# k26_baseboard_power_supply.net
KiCad netlist of a schematic drawn in Altium Designer
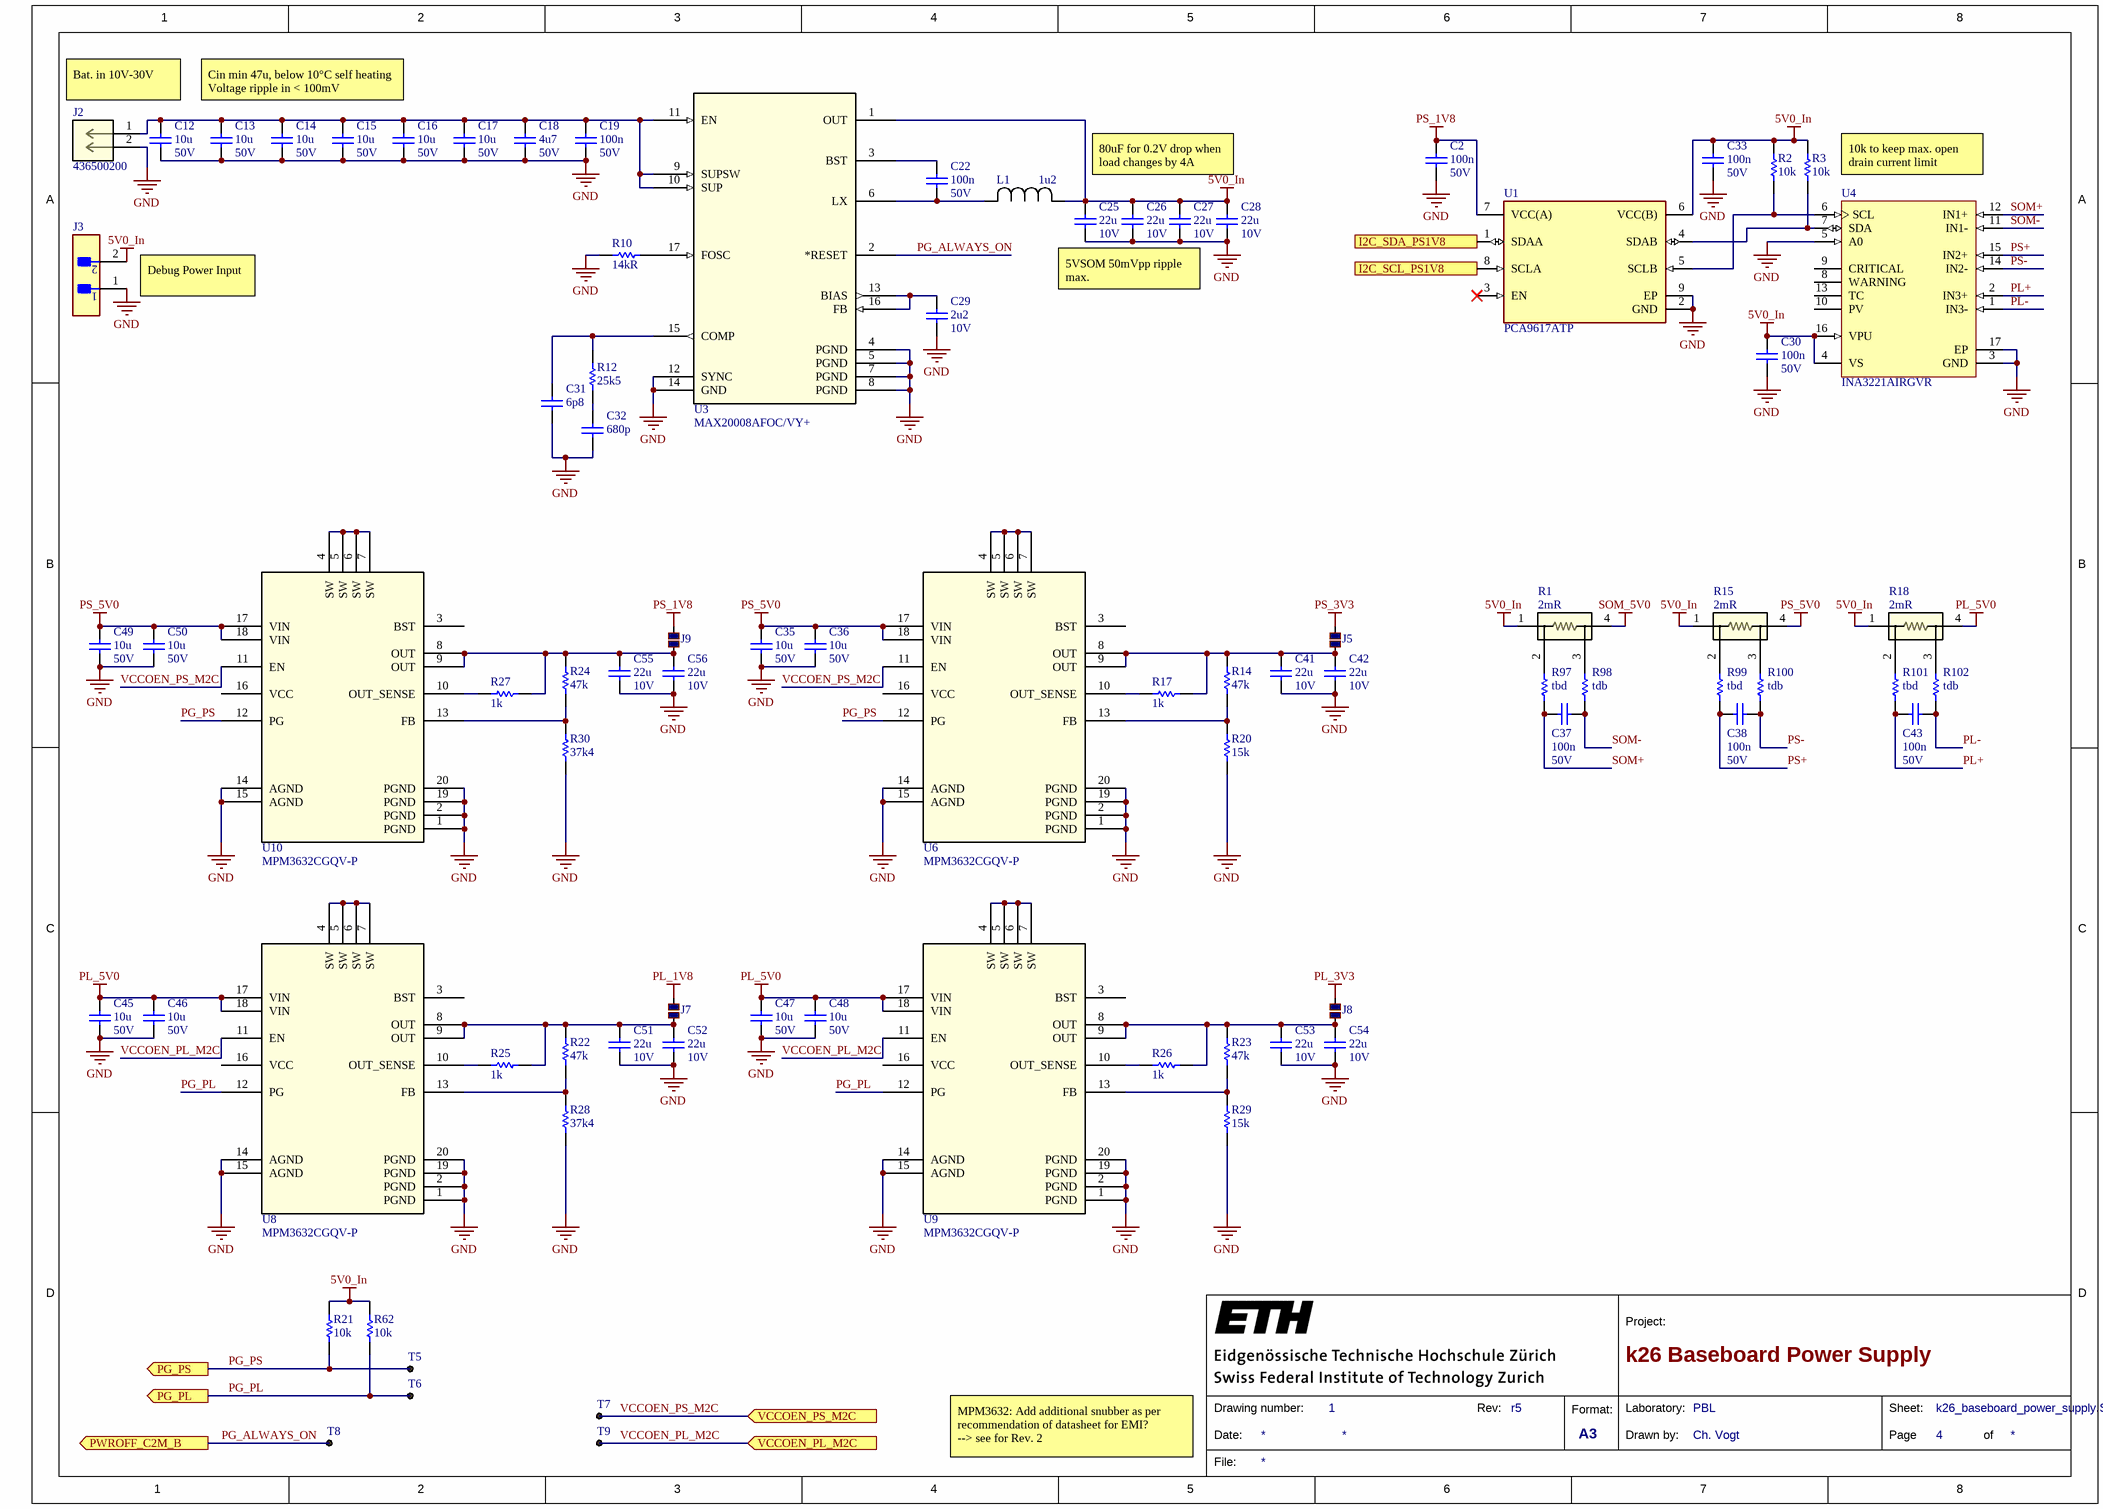
[diagram p0: k26_baseboard_power_supply.SchDoc]

(export (version "E")
  (design (tool "Eeschema 10.0.6"))
  (components
    (comp (ref "C2")
      (value "100n")
      (footprint "k26_FPGA_drone_baseboard:CAPC0402")
      (fields
        (field (name "MANUFACTURER") "Yageo")
        (field (name "MANUFACTURER PART NUMBER") "CC0402KRX5R9BB104")
        (field (name "RATED DC VOLTAGE (URDC)") "50V")
      )
      (libsource (lib "k26_FPGA_drone_baseboard") (part "cap0402"))
    )
    (comp (ref "C12")
      (value "10u")
      (footprint "k26_FPGA_drone_baseboard:CAPC1206")
      (fields
        (field (name "MANUFACTURER") "Murata")
        (field (name "MANUFACTURER PART NUMBER") "GRM31CR61H106KA12L")
        (field (name "RATED DC VOLTAGE (URDC)") "50V")
      )
      (libsource (lib "k26_FPGA_drone_baseboard") (part "cap1206"))
    )
    (comp (ref "C13")
      (value "10u")
      (footprint "k26_FPGA_drone_baseboard:CAPC1206")
      (fields
        (field (name "MANUFACTURER") "Murata")
        (field (name "MANUFACTURER PART NUMBER") "GRM31CR61H106KA12L")
        (field (name "RATED DC VOLTAGE (URDC)") "50V")
      )
      (libsource (lib "k26_FPGA_drone_baseboard") (part "cap1206"))
    )
    (comp (ref "C14")
      (value "10u")
      (footprint "k26_FPGA_drone_baseboard:CAPC1206")
      (fields
        (field (name "MANUFACTURER") "Murata")
        (field (name "MANUFACTURER PART NUMBER") "GRM31CR61H106KA12L")
        (field (name "RATED DC VOLTAGE (URDC)") "50V")
      )
      (libsource (lib "k26_FPGA_drone_baseboard") (part "cap1206"))
    )
    (comp (ref "C15")
      (value "10u")
      (footprint "k26_FPGA_drone_baseboard:CAPC1206")
      (fields
        (field (name "MANUFACTURER") "Murata")
        (field (name "MANUFACTURER PART NUMBER") "GRM31CR61H106KA12L")
        (field (name "RATED DC VOLTAGE (URDC)") "50V")
      )
      (libsource (lib "k26_FPGA_drone_baseboard") (part "cap1206"))
    )
    (comp (ref "C16")
      (value "10u")
      (footprint "k26_FPGA_drone_baseboard:CAPC1206")
      (fields
        (field (name "MANUFACTURER") "Murata")
        (field (name "MANUFACTURER PART NUMBER") "GRM31CR61H106KA12L")
        (field (name "RATED DC VOLTAGE (URDC)") "50V")
      )
      (libsource (lib "k26_FPGA_drone_baseboard") (part "cap1206"))
    )
    (comp (ref "C17")
      (value "10u")
      (footprint "k26_FPGA_drone_baseboard:CAPC1206")
      (fields
        (field (name "MANUFACTURER") "Murata")
        (field (name "MANUFACTURER PART NUMBER") "GRM31CR61H106KA12L")
        (field (name "RATED DC VOLTAGE (URDC)") "50V")
      )
      (libsource (lib "k26_FPGA_drone_baseboard") (part "cap1206"))
    )
    (comp (ref "C18")
      (value "4u7")
      (footprint "k26_FPGA_drone_baseboard:CAPC1206")
      (fields
        (field (name "MANUFACTURER") "Murata")
        (field (name "MANUFACTURER PART NUMBER") "GRM31CR71H475KA12L")
        (field (name "RATED DC VOLTAGE (URDC)") "50V")
      )
      (libsource (lib "k26_FPGA_drone_baseboard") (part "cap1206"))
    )
    (comp (ref "C19")
      (value "100n")
      (footprint "k26_FPGA_drone_baseboard:CAPC0402")
      (fields
        (field (name "MANUFACTURER") "Yageo")
        (field (name "MANUFACTURER PART NUMBER") "CC0402KRX5R9BB104")
        (field (name "RATED DC VOLTAGE (URDC)") "50V")
      )
      (libsource (lib "k26_FPGA_drone_baseboard") (part "cap0402"))
    )
    (comp (ref "C22")
      (value "100n")
      (footprint "k26_FPGA_drone_baseboard:CAPC0402")
      (fields
        (field (name "MANUFACTURER") "Yageo")
        (field (name "MANUFACTURER PART NUMBER") "CC0402KRX5R9BB104")
        (field (name "RATED DC VOLTAGE (URDC)") "50V")
      )
      (libsource (lib "k26_FPGA_drone_baseboard") (part "cap0402"))
    )
    (comp (ref "C25")
      (value "22u")
      (footprint "k26_FPGA_drone_baseboard:CAPC1206")
      (fields
        (field (name "MANUFACTURER") "Kyocera AVX")
        (field (name "MANUFACTURER PART NUMBER") "1206ZC226KAT2A")
        (field (name "RATED DC VOLTAGE (URDC)") "10V")
      )
      (libsource (lib "k26_FPGA_drone_baseboard") (part "cap1206"))
    )
    (comp (ref "C26")
      (value "22u")
      (footprint "k26_FPGA_drone_baseboard:CAPC1206")
      (fields
        (field (name "MANUFACTURER") "Kyocera AVX")
        (field (name "MANUFACTURER PART NUMBER") "1206ZC226KAT2A")
        (field (name "RATED DC VOLTAGE (URDC)") "10V")
      )
      (libsource (lib "k26_FPGA_drone_baseboard") (part "cap1206"))
    )
    (comp (ref "C27")
      (value "22u")
      (footprint "k26_FPGA_drone_baseboard:CAPC1206")
      (fields
        (field (name "MANUFACTURER") "Kyocera AVX")
        (field (name "MANUFACTURER PART NUMBER") "1206ZC226KAT2A")
        (field (name "RATED DC VOLTAGE (URDC)") "10V")
      )
      (libsource (lib "k26_FPGA_drone_baseboard") (part "cap1206"))
    )
    (comp (ref "C28")
      (value "22u")
      (footprint "k26_FPGA_drone_baseboard:CAPC1206")
      (fields
        (field (name "MANUFACTURER") "Kyocera AVX")
        (field (name "MANUFACTURER PART NUMBER") "1206ZC226KAT2A")
        (field (name "RATED DC VOLTAGE (URDC)") "10V")
      )
      (libsource (lib "k26_FPGA_drone_baseboard") (part "cap1206"))
    )
    (comp (ref "C29")
      (value "2u2")
      (footprint "k26_FPGA_drone_baseboard:CAPC0402")
      (fields
        (field (name "MANUFACTURER") "TDK")
        (field (name "MANUFACTURER PART NUMBER") "C1005X7S1A225K050BC")
        (field (name "RATED DC VOLTAGE (URDC)") "10V")
      )
      (libsource (lib "k26_FPGA_drone_baseboard") (part "cap0402"))
    )
    (comp (ref "C30")
      (value "100n")
      (footprint "k26_FPGA_drone_baseboard:CAPC0402")
      (fields
        (field (name "MANUFACTURER") "Yageo")
        (field (name "MANUFACTURER PART NUMBER") "CC0402KRX5R9BB104")
        (field (name "RATED DC VOLTAGE (URDC)") "50V")
      )
      (libsource (lib "k26_FPGA_drone_baseboard") (part "cap0402"))
    )
    (comp (ref "C31")
      (value "6p8")
      (footprint "k26_FPGA_drone_baseboard:CAPC0402")
      (fields
        (field (name "MANUFACTURER") "Kyocera AVX")
        (field (name "MANUFACTURER PART NUMBER") "04025A6R8CAT2A")
      )
      (libsource (lib "k26_FPGA_drone_baseboard") (part "cap0402"))
    )
    (comp (ref "C32")
      (value "680p")
      (footprint "k26_FPGA_drone_baseboard:CAPC0402")
      (fields
        (field (name "MANUFACTURER") "Kyocera AVX")
        (field (name "MANUFACTURER PART NUMBER") "04025C681KAT2A")
      )
      (libsource (lib "k26_FPGA_drone_baseboard") (part "cap0402"))
    )
    (comp (ref "C33")
      (value "100n")
      (footprint "k26_FPGA_drone_baseboard:CAPC0402")
      (fields
        (field (name "MANUFACTURER") "Yageo")
        (field (name "MANUFACTURER PART NUMBER") "CC0402KRX5R9BB104")
        (field (name "RATED DC VOLTAGE (URDC)") "50V")
      )
      (libsource (lib "k26_FPGA_drone_baseboard") (part "cap0402"))
    )
    (comp (ref "C35")
      (value "10u")
      (footprint "k26_FPGA_drone_baseboard:CAPC1206")
      (fields
        (field (name "MANUFACTURER") "Murata")
        (field (name "MANUFACTURER PART NUMBER") "GRM31CR61H106KA12L")
        (field (name "RATED DC VOLTAGE (URDC)") "50V")
      )
      (libsource (lib "k26_FPGA_drone_baseboard") (part "cap1206"))
    )
    (comp (ref "C36")
      (value "10u")
      (footprint "k26_FPGA_drone_baseboard:CAPC1206")
      (fields
        (field (name "MANUFACTURER") "Murata")
        (field (name "MANUFACTURER PART NUMBER") "GRM31CR61H106KA12L")
        (field (name "RATED DC VOLTAGE (URDC)") "50V")
      )
      (libsource (lib "k26_FPGA_drone_baseboard") (part "cap1206"))
    )
    (comp (ref "C37")
      (value "100n")
      (footprint "k26_FPGA_drone_baseboard:CAPC0402")
      (fields
        (field (name "MANUFACTURER") "Yageo")
        (field (name "MANUFACTURER PART NUMBER") "CC0402KRX5R9BB104")
        (field (name "RATED DC VOLTAGE (URDC)") "50V")
      )
      (libsource (lib "k26_FPGA_drone_baseboard") (part "cap0402"))
    )
    (comp (ref "C38")
      (value "100n")
      (footprint "k26_FPGA_drone_baseboard:CAPC0402")
      (fields
        (field (name "MANUFACTURER") "Yageo")
        (field (name "MANUFACTURER PART NUMBER") "CC0402KRX5R9BB104")
        (field (name "RATED DC VOLTAGE (URDC)") "50V")
      )
      (libsource (lib "k26_FPGA_drone_baseboard") (part "cap0402"))
    )
    (comp (ref "C41")
      (value "22u")
      (footprint "k26_FPGA_drone_baseboard:CAPC1206")
      (fields
        (field (name "MANUFACTURER") "Kyocera AVX")
        (field (name "MANUFACTURER PART NUMBER") "1206ZC226KAT2A")
        (field (name "RATED DC VOLTAGE (URDC)") "10V")
      )
      (libsource (lib "k26_FPGA_drone_baseboard") (part "cap1206"))
    )
    (comp (ref "C42")
      (value "22u")
      (footprint "k26_FPGA_drone_baseboard:CAPC1206")
      (fields
        (field (name "MANUFACTURER") "Kyocera AVX")
        (field (name "MANUFACTURER PART NUMBER") "1206ZC226KAT2A")
        (field (name "RATED DC VOLTAGE (URDC)") "10V")
      )
      (libsource (lib "k26_FPGA_drone_baseboard") (part "cap1206"))
    )
    (comp (ref "C43")
      (value "100n")
      (footprint "k26_FPGA_drone_baseboard:CAPC0402")
      (fields
        (field (name "MANUFACTURER") "Yageo")
        (field (name "MANUFACTURER PART NUMBER") "CC0402KRX5R9BB104")
        (field (name "RATED DC VOLTAGE (URDC)") "50V")
      )
      (libsource (lib "k26_FPGA_drone_baseboard") (part "cap0402"))
    )
    (comp (ref "C45")
      (value "10u")
      (footprint "k26_FPGA_drone_baseboard:CAPC1206")
      (fields
        (field (name "MANUFACTURER") "Murata")
        (field (name "MANUFACTURER PART NUMBER") "GRM31CR61H106KA12L")
        (field (name "RATED DC VOLTAGE (URDC)") "50V")
      )
      (libsource (lib "k26_FPGA_drone_baseboard") (part "cap1206"))
    )
    (comp (ref "C46")
      (value "10u")
      (footprint "k26_FPGA_drone_baseboard:CAPC1206")
      (fields
        (field (name "MANUFACTURER") "Murata")
        (field (name "MANUFACTURER PART NUMBER") "GRM31CR61H106KA12L")
        (field (name "RATED DC VOLTAGE (URDC)") "50V")
      )
      (libsource (lib "k26_FPGA_drone_baseboard") (part "cap1206"))
    )
    (comp (ref "C47")
      (value "10u")
      (footprint "k26_FPGA_drone_baseboard:CAPC1206")
      (fields
        (field (name "MANUFACTURER") "Murata")
        (field (name "MANUFACTURER PART NUMBER") "GRM31CR61H106KA12L")
        (field (name "RATED DC VOLTAGE (URDC)") "50V")
      )
      (libsource (lib "k26_FPGA_drone_baseboard") (part "cap1206"))
    )
    (comp (ref "C48")
      (value "10u")
      (footprint "k26_FPGA_drone_baseboard:CAPC1206")
      (fields
        (field (name "MANUFACTURER") "Murata")
        (field (name "MANUFACTURER PART NUMBER") "GRM31CR61H106KA12L")
        (field (name "RATED DC VOLTAGE (URDC)") "50V")
      )
      (libsource (lib "k26_FPGA_drone_baseboard") (part "cap1206"))
    )
    (comp (ref "C49")
      (value "10u")
      (footprint "k26_FPGA_drone_baseboard:CAPC1206")
      (fields
        (field (name "MANUFACTURER") "Murata")
        (field (name "MANUFACTURER PART NUMBER") "GRM31CR61H106KA12L")
        (field (name "RATED DC VOLTAGE (URDC)") "50V")
      )
      (libsource (lib "k26_FPGA_drone_baseboard") (part "cap1206"))
    )
    (comp (ref "C50")
      (value "10u")
      (footprint "k26_FPGA_drone_baseboard:CAPC1206")
      (fields
        (field (name "MANUFACTURER") "Murata")
        (field (name "MANUFACTURER PART NUMBER") "GRM31CR61H106KA12L")
        (field (name "RATED DC VOLTAGE (URDC)") "50V")
      )
      (libsource (lib "k26_FPGA_drone_baseboard") (part "cap1206"))
    )
    (comp (ref "C51")
      (value "22u")
      (footprint "k26_FPGA_drone_baseboard:CAPC1206")
      (fields
        (field (name "MANUFACTURER") "Kyocera AVX")
        (field (name "MANUFACTURER PART NUMBER") "1206ZC226KAT2A")
        (field (name "RATED DC VOLTAGE (URDC)") "10V")
      )
      (libsource (lib "k26_FPGA_drone_baseboard") (part "cap1206"))
    )
    (comp (ref "C52")
      (value "22u")
      (footprint "k26_FPGA_drone_baseboard:CAPC1206")
      (fields
        (field (name "MANUFACTURER") "Kyocera AVX")
        (field (name "MANUFACTURER PART NUMBER") "1206ZC226KAT2A")
        (field (name "RATED DC VOLTAGE (URDC)") "10V")
      )
      (libsource (lib "k26_FPGA_drone_baseboard") (part "cap1206"))
    )
    (comp (ref "C53")
      (value "22u")
      (footprint "k26_FPGA_drone_baseboard:CAPC1206")
      (fields
        (field (name "MANUFACTURER") "Kyocera AVX")
        (field (name "MANUFACTURER PART NUMBER") "1206ZC226KAT2A")
        (field (name "RATED DC VOLTAGE (URDC)") "10V")
      )
      (libsource (lib "k26_FPGA_drone_baseboard") (part "cap1206"))
    )
    (comp (ref "C54")
      (value "22u")
      (footprint "k26_FPGA_drone_baseboard:CAPC1206")
      (fields
        (field (name "MANUFACTURER") "Kyocera AVX")
        (field (name "MANUFACTURER PART NUMBER") "1206ZC226KAT2A")
        (field (name "RATED DC VOLTAGE (URDC)") "10V")
      )
      (libsource (lib "k26_FPGA_drone_baseboard") (part "cap1206"))
    )
    (comp (ref "C55")
      (value "22u")
      (footprint "k26_FPGA_drone_baseboard:CAPC1206")
      (fields
        (field (name "MANUFACTURER") "Kyocera AVX")
        (field (name "MANUFACTURER PART NUMBER") "1206ZC226KAT2A")
        (field (name "RATED DC VOLTAGE (URDC)") "10V")
      )
      (libsource (lib "k26_FPGA_drone_baseboard") (part "cap1206"))
    )
    (comp (ref "C56")
      (value "22u")
      (footprint "k26_FPGA_drone_baseboard:CAPC1206")
      (fields
        (field (name "MANUFACTURER") "Kyocera AVX")
        (field (name "MANUFACTURER PART NUMBER") "1206ZC226KAT2A")
        (field (name "RATED DC VOLTAGE (URDC)") "10V")
      )
      (libsource (lib "k26_FPGA_drone_baseboard") (part "cap1206"))
    )
    (comp (ref "J2")
      (value "436500200")
      (footprint "CON_436500200_MOL")
      (description "Board Connector, 2 Contact(s), 1 Row(s), Male, Right Angle, Solder Terminal")
      (fields
        (field (name "MANUFACTURER") "Molex")
        (field (name "MANUFACTURER PART NUMBER") "0436500200")
        (field (name "COPYRIGHT") "Copyright (C) 2024 Ultra Librarian. All rights reserved.")
      )
      (libsource (lib "k26_FPGA_drone_baseboard") (part "436500200"))
    )
    (comp (ref "J3")
      (value "~")
      (footprint "FP-TSW-102-07-S-S-MFG")
      (description "CONN HEADER VERT 2POS 2.54MM")
      (libsource (lib "k26_FPGA_drone_baseboard") (part "3bc925449376181038e59eaffc5286c"))
    )
    (comp (ref "J5")
      (value "CMP-00005-5")
      (footprint "Big Solder Jumper")
      (libsource (lib "k26_FPGA_drone_baseboard") (part "CMP-00005-5"))
    )
    (comp (ref "J7")
      (value "CMP-00005-5")
      (footprint "Big Solder Jumper")
      (libsource (lib "k26_FPGA_drone_baseboard") (part "CMP-00005-5"))
    )
    (comp (ref "J8")
      (value "CMP-00005-5")
      (footprint "Big Solder Jumper")
      (libsource (lib "k26_FPGA_drone_baseboard") (part "CMP-00005-5"))
    )
    (comp (ref "J9")
      (value "CMP-00005-5")
      (footprint "Big Solder Jumper")
      (libsource (lib "k26_FPGA_drone_baseboard") (part "CMP-00005-5"))
    )
    (comp (ref "L1")
      (value "XGL5050-122MEC")
      (footprint "IND_XGL5050_COC")
      (description "General Purpose Inductor, 1.2uH, 20%, 1 Element, Composite-Core, SMD, 2221")
      (fields
        (field (name "MANUFACTURER") "Coilcraft")
        (field (name "PARAMETER 1") "1u2")
        (field (name "COPYRIGHT") "Copyright (C) 2023 Ultra Librarian. All rights reserved.")
      )
      (libsource (lib "k26_FPGA_drone_baseboard") (part "XGL5050-122MEC"))
    )
    (comp (ref "R1")
      (value "CST0612-FC-R002E")
      (footprint "CST0612-FC-R002E_BRN")
      (description "No Description Available")
      (fields
        (field (name "RES") "2mR")
        (field (name "COPYRIGHT") "Copyright (C) 2023 Ultra Librarian. All rights reserved.")
      )
      (libsource (lib "k26_FPGA_drone_baseboard") (part "CST0612-FC-R002E"))
    )
    (comp (ref "R2")
      (value "10k")
      (footprint "k26_FPGA_drone_baseboard:RES0402")
      (fields
        (field (name "MANUFACTURER") "Panasonic")
        (field (name "MANUFACTURER PART NUMBER") "ERJ-2RKF1002X")
        (field (name "TOLERANCE") "1%")
      )
      (libsource (lib "k26_FPGA_drone_baseboard") (part "res0402"))
    )
    (comp (ref "R3")
      (value "10k")
      (footprint "k26_FPGA_drone_baseboard:RES0402")
      (fields
        (field (name "MANUFACTURER") "Panasonic")
        (field (name "MANUFACTURER PART NUMBER") "ERJ-2RKF1002X")
        (field (name "TOLERANCE") "1%")
      )
      (libsource (lib "k26_FPGA_drone_baseboard") (part "res0402"))
    )
    (comp (ref "R10")
      (value "14kR")
      (footprint "k26_FPGA_drone_baseboard:RES0402")
      (fields
        (field (name "MANUFACTURER") "Vishay")
        (field (name "MANUFACTURER PART NUMBER") "CRCW040214K0FKED")
        (field (name "TOLERANCE") "1%")
      )
      (libsource (lib "k26_FPGA_drone_baseboard") (part "res0402"))
    )
    (comp (ref "R12")
      (value "25k5")
      (footprint "k26_FPGA_drone_baseboard:RES0402")
      (fields
        (field (name "MANUFACTURER") "Vishay")
        (field (name "MANUFACTURER PART NUMBER") "CRCW040225K5FKED")
        (field (name "TOLERANCE") "1%")
      )
      (libsource (lib "k26_FPGA_drone_baseboard") (part "res0402"))
    )
    (comp (ref "R14")
      (value "47k")
      (footprint "k26_FPGA_drone_baseboard:RES0402")
      (fields
        (field (name "MANUFACTURER") "Vishay")
        (field (name "MANUFACTURER PART NUMBER") "CRCW040247K0FKED")
        (field (name "TOLERANCE") "1%")
      )
      (libsource (lib "k26_FPGA_drone_baseboard") (part "res0402"))
    )
    (comp (ref "R15")
      (value "CST0612-FC-R002E")
      (footprint "CST0612-FC-R002E_BRN")
      (description "No Description Available")
      (fields
        (field (name "RES") "2mR")
        (field (name "COPYRIGHT") "Copyright (C) 2023 Ultra Librarian. All rights reserved.")
      )
      (libsource (lib "k26_FPGA_drone_baseboard") (part "CST0612-FC-R002E"))
    )
    (comp (ref "R17")
      (value "1k")
      (footprint "k26_FPGA_drone_baseboard:RES0402")
      (fields
        (field (name "MANUFACTURER") "Yageo")
        (field (name "MANUFACTURER PART NUMBER") "RC0402FR-071KL")
        (field (name "TOLERANCE") "1%")
      )
      (libsource (lib "k26_FPGA_drone_baseboard") (part "res0402"))
    )
    (comp (ref "R18")
      (value "CST0612-FC-R002E")
      (footprint "CST0612-FC-R002E_BRN")
      (description "No Description Available")
      (fields
        (field (name "RES") "2mR")
        (field (name "COPYRIGHT") "Copyright (C) 2023 Ultra Librarian. All rights reserved.")
      )
      (libsource (lib "k26_FPGA_drone_baseboard") (part "CST0612-FC-R002E"))
    )
    (comp (ref "R20")
      (value "15k")
      (footprint "k26_FPGA_drone_baseboard:RES0402")
      (fields
        (field (name "MANUFACTURER") "Panasonic")
        (field (name "MANUFACTURER PART NUMBER") "ERJ-2RKF1502X")
        (field (name "TOLERANCE") "1%")
      )
      (libsource (lib "k26_FPGA_drone_baseboard") (part "res0402"))
    )
    (comp (ref "R21")
      (value "10k")
      (footprint "k26_FPGA_drone_baseboard:RES0402")
      (fields
        (field (name "MANUFACTURER") "Panasonic")
        (field (name "MANUFACTURER PART NUMBER") "ERJ-2RKF1002X")
        (field (name "TOLERANCE") "1%")
      )
      (libsource (lib "k26_FPGA_drone_baseboard") (part "res0402"))
    )
    (comp (ref "R22")
      (value "47k")
      (footprint "k26_FPGA_drone_baseboard:RES0402")
      (fields
        (field (name "MANUFACTURER") "Vishay")
        (field (name "MANUFACTURER PART NUMBER") "CRCW040247K0FKED")
        (field (name "TOLERANCE") "1%")
      )
      (libsource (lib "k26_FPGA_drone_baseboard") (part "res0402"))
    )
    (comp (ref "R23")
      (value "47k")
      (footprint "k26_FPGA_drone_baseboard:RES0402")
      (fields
        (field (name "MANUFACTURER") "Vishay")
        (field (name "MANUFACTURER PART NUMBER") "CRCW040247K0FKED")
        (field (name "TOLERANCE") "1%")
      )
      (libsource (lib "k26_FPGA_drone_baseboard") (part "res0402"))
    )
    (comp (ref "R24")
      (value "47k")
      (footprint "k26_FPGA_drone_baseboard:RES0402")
      (fields
        (field (name "MANUFACTURER") "Vishay")
        (field (name "MANUFACTURER PART NUMBER") "CRCW040247K0FKED")
        (field (name "TOLERANCE") "1%")
      )
      (libsource (lib "k26_FPGA_drone_baseboard") (part "res0402"))
    )
    (comp (ref "R25")
      (value "1k")
      (footprint "k26_FPGA_drone_baseboard:RES0402")
      (fields
        (field (name "MANUFACTURER") "Yageo")
        (field (name "MANUFACTURER PART NUMBER") "RC0402FR-071KL")
        (field (name "TOLERANCE") "1%")
      )
      (libsource (lib "k26_FPGA_drone_baseboard") (part "res0402"))
    )
    (comp (ref "R26")
      (value "1k")
      (footprint "k26_FPGA_drone_baseboard:RES0402")
      (fields
        (field (name "MANUFACTURER") "Yageo")
        (field (name "MANUFACTURER PART NUMBER") "RC0402FR-071KL")
        (field (name "TOLERANCE") "1%")
      )
      (libsource (lib "k26_FPGA_drone_baseboard") (part "res0402"))
    )
    (comp (ref "R27")
      (value "1k")
      (footprint "k26_FPGA_drone_baseboard:RES0402")
      (fields
        (field (name "MANUFACTURER") "Yageo")
        (field (name "MANUFACTURER PART NUMBER") "RC0402FR-071KL")
        (field (name "TOLERANCE") "1%")
      )
      (libsource (lib "k26_FPGA_drone_baseboard") (part "res0402"))
    )
    (comp (ref "R28")
      (value "37k4")
      (footprint "k26_FPGA_drone_baseboard:RES0402")
      (fields
        (field (name "MANUFACTURER") "Panasonic")
        (field (name "MANUFACTURER PART NUMBER") "ERJ-2RKF3742X")
        (field (name "TOLERANCE") "1%")
      )
      (libsource (lib "k26_FPGA_drone_baseboard") (part "res0402"))
    )
    (comp (ref "R29")
      (value "15k")
      (footprint "k26_FPGA_drone_baseboard:RES0402")
      (fields
        (field (name "MANUFACTURER") "Panasonic")
        (field (name "MANUFACTURER PART NUMBER") "ERJ-2RKF1502X")
        (field (name "TOLERANCE") "1%")
      )
      (libsource (lib "k26_FPGA_drone_baseboard") (part "res0402"))
    )
    (comp (ref "R30")
      (value "37k4")
      (footprint "k26_FPGA_drone_baseboard:RES0402")
      (fields
        (field (name "MANUFACTURER") "Panasonic")
        (field (name "MANUFACTURER PART NUMBER") "ERJ-2RKF3742X")
        (field (name "TOLERANCE") "1%")
      )
      (libsource (lib "k26_FPGA_drone_baseboard") (part "res0402"))
    )
    (comp (ref "R62")
      (value "10k")
      (footprint "k26_FPGA_drone_baseboard:RES0402")
      (fields
        (field (name "MANUFACTURER") "Panasonic")
        (field (name "MANUFACTURER PART NUMBER") "ERJ-2RKF1002X")
        (field (name "TOLERANCE") "1%")
      )
      (libsource (lib "k26_FPGA_drone_baseboard") (part "res0402"))
    )
    (comp (ref "R97")
      (value "tbd")
      (footprint "k26_FPGA_drone_baseboard:RES0402")
      (fields
        (field (name "MANUFACTURER") "Yageo")
        (field (name "MANUFACTURER PART NUMBER") "RC0402FR-071KL")
        (field (name "TOLERANCE") "1%")
      )
      (libsource (lib "k26_FPGA_drone_baseboard") (part "res0402"))
    )
    (comp (ref "R98")
      (value "tdb")
      (footprint "k26_FPGA_drone_baseboard:RES0402")
      (fields
        (field (name "MANUFACTURER") "Yageo")
        (field (name "MANUFACTURER PART NUMBER") "RC0402FR-071KL")
        (field (name "TOLERANCE") "1%")
      )
      (libsource (lib "k26_FPGA_drone_baseboard") (part "res0402"))
    )
    (comp (ref "R99")
      (value "tbd")
      (footprint "k26_FPGA_drone_baseboard:RES0402")
      (fields
        (field (name "MANUFACTURER") "Yageo")
        (field (name "MANUFACTURER PART NUMBER") "RC0402FR-071KL")
        (field (name "TOLERANCE") "1%")
      )
      (libsource (lib "k26_FPGA_drone_baseboard") (part "res0402"))
    )
    (comp (ref "R100")
      (value "tdb")
      (footprint "k26_FPGA_drone_baseboard:RES0402")
      (fields
        (field (name "MANUFACTURER") "Yageo")
        (field (name "MANUFACTURER PART NUMBER") "RC0402FR-071KL")
        (field (name "TOLERANCE") "1%")
      )
      (libsource (lib "k26_FPGA_drone_baseboard") (part "res0402"))
    )
    (comp (ref "R101")
      (value "tbd")
      (footprint "k26_FPGA_drone_baseboard:RES0402")
      (fields
        (field (name "MANUFACTURER") "Yageo")
        (field (name "MANUFACTURER PART NUMBER") "RC0402FR-071KL")
        (field (name "TOLERANCE") "1%")
      )
      (libsource (lib "k26_FPGA_drone_baseboard") (part "res0402"))
    )
    (comp (ref "R102")
      (value "tdb")
      (footprint "k26_FPGA_drone_baseboard:RES0402")
      (fields
        (field (name "MANUFACTURER") "Yageo")
        (field (name "MANUFACTURER PART NUMBER") "RC0402FR-071KL")
        (field (name "TOLERANCE") "1%")
      )
      (libsource (lib "k26_FPGA_drone_baseboard") (part "res0402"))
    )
    (comp (ref "T5")
      (value "~")
      (footprint "Pad-1mm")
      (description "1mm SMT Test Pad")
      (libsource (lib "k26_FPGA_drone_baseboard") (part "Test Pad"))
    )
    (comp (ref "T6")
      (value "~")
      (footprint "Pad-1mm")
      (description "1mm SMT Test Pad")
      (libsource (lib "k26_FPGA_drone_baseboard") (part "Test Pad"))
    )
    (comp (ref "T7")
      (value "~")
      (footprint "Pad-1mm")
      (description "1mm SMT Test Pad")
      (libsource (lib "k26_FPGA_drone_baseboard") (part "Test Pad"))
    )
    (comp (ref "T8")
      (value "~")
      (footprint "Pad-1mm")
      (description "1mm SMT Test Pad")
      (libsource (lib "k26_FPGA_drone_baseboard") (part "Test Pad"))
    )
    (comp (ref "T9")
      (value "~")
      (footprint "Pad-1mm")
      (description "1mm SMT Test Pad")
      (libsource (lib "k26_FPGA_drone_baseboard") (part "Test Pad"))
    )
    (comp (ref "U1")
      (value "PCA9617ATP")
      (footprint "FP-SOT1069-2-MFG")
      (description "IC REDRIVER I2C 1CH 1MHZ 8HWSON")
      (libsource (lib "k26_FPGA_drone_baseboard") (part "91d4d44e6b01ffaf70a860af717f933"))
    )
    (comp (ref "U3")
      (value "MAX20008AFOC/VY+")
      (footprint "21-100155B_F173A3FY+1_MXM")
      (description "No Description Available")
      (fields (field (name "COPYRIGHT") "Copyright (C) 2022 Ultra Librarian. All rights reserved."))
      (libsource (lib "k26_FPGA_drone_baseboard") (part "MAX20008AFOC/VY+"))
    )
    (comp (ref "U4")
      (value "INA3221AIRGVR")
      (footprint "RGV0016A_V")
      (fields (field (name "MANUFACTURER") "Texas Instruments"))
      (libsource (lib "k26_FPGA_drone_baseboard") (part "TI-INA3221-RGV-16"))
    )
    (comp (ref "U6")
      (value "MPM3632CGQV-P")
      (footprint "k26_FPGA_drone_baseboard:QFN3p0x5p0x1p6_MPM3632C_MNP")
      (description "No Description Available")
      (fields (field (name "COPYRIGHT") "Copyright (C) 2022 Ultra Librarian. All rights reserved."))
      (libsource (lib "k26_FPGA_drone_baseboard") (part "MPM3632CGQV-P"))
    )
    (comp (ref "U8")
      (value "MPM3632CGQV-P")
      (footprint "k26_FPGA_drone_baseboard:QFN3p0x5p0x1p6_MPM3632C_MNP")
      (description "No Description Available")
      (fields (field (name "COPYRIGHT") "Copyright (C) 2022 Ultra Librarian. All rights reserved."))
      (libsource (lib "k26_FPGA_drone_baseboard") (part "MPM3632CGQV-P"))
    )
    (comp (ref "U9")
      (value "MPM3632CGQV-P")
      (footprint "k26_FPGA_drone_baseboard:QFN3p0x5p0x1p6_MPM3632C_MNP")
      (description "No Description Available")
      (fields (field (name "COPYRIGHT") "Copyright (C) 2022 Ultra Librarian. All rights reserved."))
      (libsource (lib "k26_FPGA_drone_baseboard") (part "MPM3632CGQV-P"))
    )
    (comp (ref "U10")
      (value "MPM3632CGQV-P")
      (footprint "k26_FPGA_drone_baseboard:QFN3p0x5p0x1p6_MPM3632C_MNP")
      (description "No Description Available")
      (fields (field (name "COPYRIGHT") "Copyright (C) 2022 Ultra Librarian. All rights reserved."))
      (libsource (lib "k26_FPGA_drone_baseboard") (part "MPM3632CGQV-P"))
    )
  )
  (nets
    (net (code "1") (name "/I2C_SCL_PS1V8") (class "Default")
      (node (ref "U1") (pin "8") (pinfunction "SCLA_8") (pintype "input"))
    )
    (net (code "2") (name "/I2C_SDA_PS1V8") (class "Default")
      (node (ref "U1") (pin "1") (pinfunction "SDAA_1") (pintype "bidirectional"))
    )
    (net (code "3") (name "/PG_ALWAYS_ON") (class "Default")
      (node (ref "T8") (pin "1") (pinfunction "1_1") (pintype "passive"))
      (node (ref "U3") (pin "2") (pinfunction "*RESET_2") (pintype "passive"))
    )
    (net (code "4") (name "/PG_PL") (class "Default")
      (node (ref "R62") (pin "1") (pinfunction "1_1") (pintype "passive"))
      (node (ref "T6") (pin "1") (pinfunction "1_1") (pintype "passive"))
      (node (ref "U8") (pin "12") (pinfunction "PG_12") (pintype "passive"))
      (node (ref "U9") (pin "12") (pinfunction "PG_12") (pintype "passive"))
    )
    (net (code "5") (name "/PG_PS") (class "Default")
      (node (ref "R21") (pin "1") (pinfunction "1_1") (pintype "passive"))
      (node (ref "T5") (pin "1") (pinfunction "1_1") (pintype "passive"))
      (node (ref "U10") (pin "12") (pinfunction "PG_12") (pintype "passive"))
      (node (ref "U6") (pin "12") (pinfunction "PG_12") (pintype "passive"))
    )
    (net (code "6") (name "/PL+") (class "Default")
      (node (ref "C43") (pin "2") (pinfunction "2_2") (pintype "passive"))
      (node (ref "R101") (pin "1") (pinfunction "1_1") (pintype "passive"))
      (node (ref "U4") (pin "2") (pinfunction "IN3+_2") (pintype "input"))
    )
    (net (code "7") (name "/PL-") (class "Default")
      (node (ref "C43") (pin "1") (pinfunction "1_1") (pintype "passive"))
      (node (ref "R102") (pin "1") (pinfunction "1_1") (pintype "passive"))
      (node (ref "U4") (pin "1") (pinfunction "IN3-_1") (pintype "input"))
    )
    (net (code "8") (name "/PS+") (class "Default")
      (node (ref "C38") (pin "2") (pinfunction "2_2") (pintype "passive"))
      (node (ref "R99") (pin "1") (pinfunction "1_1") (pintype "passive"))
      (node (ref "U4") (pin "15") (pinfunction "IN2+_15") (pintype "input"))
    )
    (net (code "9") (name "/PS-") (class "Default")
      (node (ref "C38") (pin "1") (pinfunction "1_1") (pintype "passive"))
      (node (ref "R100") (pin "1") (pinfunction "1_1") (pintype "passive"))
      (node (ref "U4") (pin "14") (pinfunction "IN2-_14") (pintype "input"))
    )
    (net (code "10") (name "/SOM+") (class "Default")
      (node (ref "C37") (pin "2") (pinfunction "2_2") (pintype "passive"))
      (node (ref "R97") (pin "1") (pinfunction "1_1") (pintype "passive"))
      (node (ref "U4") (pin "12") (pinfunction "IN1+_12") (pintype "input"))
    )
    (net (code "11") (name "/SOM-") (class "Default")
      (node (ref "C37") (pin "1") (pinfunction "1_1") (pintype "passive"))
      (node (ref "R98") (pin "1") (pinfunction "1_1") (pintype "passive"))
      (node (ref "U4") (pin "11") (pinfunction "IN1-_11") (pintype "input"))
    )
    (net (code "12") (name "/VCCOEN_PL_M2C") (class "Default")
      (node (ref "T9") (pin "1") (pinfunction "1_1") (pintype "passive"))
      (node (ref "U8") (pin "11") (pinfunction "EN_11") (pintype "passive"))
      (node (ref "U9") (pin "11") (pinfunction "EN_11") (pintype "passive"))
    )
    (net (code "13") (name "/VCCOEN_PS_M2C") (class "Default")
      (node (ref "T7") (pin "1") (pinfunction "1_1") (pintype "passive"))
      (node (ref "U10") (pin "11") (pinfunction "EN_11") (pintype "passive"))
      (node (ref "U6") (pin "11") (pinfunction "EN_11") (pintype "passive"))
    )
    (net (code "14") (name "5V0_In") (class "Default")
      (node (ref "C25") (pin "2") (pinfunction "2_2") (pintype "passive"))
      (node (ref "C26") (pin "2") (pinfunction "2_2") (pintype "passive"))
      (node (ref "C27") (pin "2") (pinfunction "2_2") (pintype "passive"))
      (node (ref "C28") (pin "2") (pinfunction "2_2") (pintype "passive"))
      (node (ref "C30") (pin "2") (pinfunction "2_2") (pintype "passive"))
      (node (ref "C33") (pin "2") (pinfunction "2_2") (pintype "passive"))
      (node (ref "J3") (pin "2") (pinfunction "2_2") (pintype "passive"))
      (node (ref "L1") (pin "1") (pinfunction "1_1") (pintype "passive"))
      (node (ref "R1") (pin "1") (pinfunction "1_1") (pintype "passive"))
      (node (ref "R15") (pin "1") (pinfunction "1_1") (pintype "passive"))
      (node (ref "R18") (pin "1") (pinfunction "1_1") (pintype "passive"))
      (node (ref "R2") (pin "2") (pinfunction "2_2") (pintype "passive"))
      (node (ref "R21") (pin "2") (pinfunction "2_2") (pintype "passive"))
      (node (ref "R3") (pin "2") (pinfunction "2_2") (pintype "passive"))
      (node (ref "R62") (pin "2") (pinfunction "2_2") (pintype "passive"))
      (node (ref "U1") (pin "6") (pinfunction "VCC(B)_6") (pintype "power_in"))
      (node (ref "U3") (pin "1") (pinfunction "OUT_1") (pintype "passive"))
      (node (ref "U4") (pin "16") (pinfunction "VPU_16") (pintype "input"))
      (node (ref "U4") (pin "4") (pinfunction "VS_4") (pintype "power_in"))
    )
    (net (code "15") (name "GND") (class "Default")
      (node (ref "C12") (pin "1") (pinfunction "1_1") (pintype "passive"))
      (node (ref "C13") (pin "1") (pinfunction "1_1") (pintype "passive"))
      (node (ref "C14") (pin "1") (pinfunction "1_1") (pintype "passive"))
      (node (ref "C15") (pin "1") (pinfunction "1_1") (pintype "passive"))
      (node (ref "C16") (pin "1") (pinfunction "1_1") (pintype "passive"))
      (node (ref "C17") (pin "1") (pinfunction "1_1") (pintype "passive"))
      (node (ref "C18") (pin "1") (pinfunction "1_1") (pintype "passive"))
      (node (ref "C19") (pin "1") (pinfunction "1_1") (pintype "passive"))
      (node (ref "C2") (pin "1") (pinfunction "1_1") (pintype "passive"))
      (node (ref "C25") (pin "1") (pinfunction "1_1") (pintype "passive"))
      (node (ref "C26") (pin "1") (pinfunction "1_1") (pintype "passive"))
      (node (ref "C27") (pin "1") (pinfunction "1_1") (pintype "passive"))
      (node (ref "C28") (pin "1") (pinfunction "1_1") (pintype "passive"))
      (node (ref "C29") (pin "1") (pinfunction "1_1") (pintype "passive"))
      (node (ref "C30") (pin "1") (pinfunction "1_1") (pintype "passive"))
      (node (ref "C31") (pin "1") (pinfunction "1_1") (pintype "passive"))
      (node (ref "C32") (pin "1") (pinfunction "1_1") (pintype "passive"))
      (node (ref "C33") (pin "1") (pinfunction "1_1") (pintype "passive"))
      (node (ref "C35") (pin "1") (pinfunction "1_1") (pintype "passive"))
      (node (ref "C36") (pin "1") (pinfunction "1_1") (pintype "passive"))
      (node (ref "C41") (pin "1") (pinfunction "1_1") (pintype "passive"))
      (node (ref "C42") (pin "1") (pinfunction "1_1") (pintype "passive"))
      (node (ref "C45") (pin "1") (pinfunction "1_1") (pintype "passive"))
      (node (ref "C46") (pin "1") (pinfunction "1_1") (pintype "passive"))
      (node (ref "C47") (pin "1") (pinfunction "1_1") (pintype "passive"))
      (node (ref "C48") (pin "1") (pinfunction "1_1") (pintype "passive"))
      (node (ref "C49") (pin "1") (pinfunction "1_1") (pintype "passive"))
      (node (ref "C50") (pin "1") (pinfunction "1_1") (pintype "passive"))
      (node (ref "C51") (pin "1") (pinfunction "1_1") (pintype "passive"))
      (node (ref "C52") (pin "1") (pinfunction "1_1") (pintype "passive"))
      (node (ref "C53") (pin "1") (pinfunction "1_1") (pintype "passive"))
      (node (ref "C54") (pin "1") (pinfunction "1_1") (pintype "passive"))
      (node (ref "C55") (pin "1") (pinfunction "1_1") (pintype "passive"))
      (node (ref "C56") (pin "1") (pinfunction "1_1") (pintype "passive"))
      (node (ref "J2") (pin "2") (pinfunction "2_2") (pintype "passive"))
      (node (ref "J3") (pin "1") (pinfunction "1_1") (pintype "passive"))
      (node (ref "R10") (pin "1") (pinfunction "1_1") (pintype "passive"))
      (node (ref "R20") (pin "1") (pinfunction "1_1") (pintype "passive"))
      (node (ref "R28") (pin "1") (pinfunction "1_1") (pintype "passive"))
      (node (ref "R29") (pin "1") (pinfunction "1_1") (pintype "passive"))
      (node (ref "R30") (pin "1") (pinfunction "1_1") (pintype "passive"))
      (node (ref "U1") (pin "2") (pinfunction "GND_2") (pintype "power_in"))
      (node (ref "U1") (pin "9") (pinfunction "EP_9") (pintype "power_in"))
      (node (ref "U10") (pin "1") (pinfunction "PGND_1") (pintype "passive"))
      (node (ref "U10") (pin "14") (pinfunction "AGND_14") (pintype "passive"))
      (node (ref "U10") (pin "15") (pinfunction "AGND_15") (pintype "passive"))
      (node (ref "U10") (pin "19") (pinfunction "PGND_19") (pintype "passive"))
      (node (ref "U10") (pin "2") (pinfunction "PGND_2") (pintype "passive"))
      (node (ref "U10") (pin "20") (pinfunction "PGND_20") (pintype "passive"))
      (node (ref "U3") (pin "12") (pinfunction "SYNC_12") (pintype "passive"))
      (node (ref "U3") (pin "14") (pinfunction "GND_14") (pintype "power_in"))
      (node (ref "U3") (pin "4") (pinfunction "PGND_4") (pintype "power_in"))
      (node (ref "U3") (pin "5") (pinfunction "PGND_5") (pintype "power_in"))
      (node (ref "U3") (pin "7") (pinfunction "PGND_7") (pintype "power_in"))
      (node (ref "U3") (pin "8") (pinfunction "PGND_8") (pintype "power_in"))
      (node (ref "U4") (pin "17") (pinfunction "EP_17") (pintype "passive"))
      (node (ref "U4") (pin "3") (pinfunction "GND_3") (pintype "power_in"))
      (node (ref "U4") (pin "5") (pinfunction "A0_5") (pintype "input"))
      (node (ref "U6") (pin "1") (pinfunction "PGND_1") (pintype "passive"))
      (node (ref "U6") (pin "14") (pinfunction "AGND_14") (pintype "passive"))
      (node (ref "U6") (pin "15") (pinfunction "AGND_15") (pintype "passive"))
      (node (ref "U6") (pin "19") (pinfunction "PGND_19") (pintype "passive"))
      (node (ref "U6") (pin "2") (pinfunction "PGND_2") (pintype "passive"))
      (node (ref "U6") (pin "20") (pinfunction "PGND_20") (pintype "passive"))
      (node (ref "U8") (pin "1") (pinfunction "PGND_1") (pintype "passive"))
      (node (ref "U8") (pin "14") (pinfunction "AGND_14") (pintype "passive"))
      (node (ref "U8") (pin "15") (pinfunction "AGND_15") (pintype "passive"))
      (node (ref "U8") (pin "19") (pinfunction "PGND_19") (pintype "passive"))
      (node (ref "U8") (pin "2") (pinfunction "PGND_2") (pintype "passive"))
      (node (ref "U8") (pin "20") (pinfunction "PGND_20") (pintype "passive"))
      (node (ref "U9") (pin "1") (pinfunction "PGND_1") (pintype "passive"))
      (node (ref "U9") (pin "14") (pinfunction "AGND_14") (pintype "passive"))
      (node (ref "U9") (pin "15") (pinfunction "AGND_15") (pintype "passive"))
      (node (ref "U9") (pin "19") (pinfunction "PGND_19") (pintype "passive"))
      (node (ref "U9") (pin "2") (pinfunction "PGND_2") (pintype "passive"))
      (node (ref "U9") (pin "20") (pinfunction "PGND_20") (pintype "passive"))
    )
    (net (code "16") (name "Net-(C32-Pad2)") (class "Default")
      (node (ref "C32") (pin "2") (pinfunction "2_2") (pintype "passive"))
      (node (ref "R12") (pin "1") (pinfunction "1_1") (pintype "passive"))
    )
    (net (code "17") (name "Net-(C41-Pad2)") (class "Default")
      (node (ref "C41") (pin "2") (pinfunction "2_2") (pintype "passive"))
      (node (ref "C42") (pin "2") (pinfunction "2_2") (pintype "passive"))
      (node (ref "J5") (pin "2") (pintype "passive"))
      (node (ref "R14") (pin "2") (pinfunction "2_2") (pintype "passive"))
      (node (ref "R17") (pin "2") (pinfunction "2_2") (pintype "passive"))
      (node (ref "U6") (pin "8") (pinfunction "OUT_8") (pintype "passive"))
      (node (ref "U6") (pin "9") (pinfunction "OUT_9") (pintype "passive"))
    )
    (net (code "18") (name "Net-(C51-Pad2)") (class "Default")
      (node (ref "C51") (pin "2") (pinfunction "2_2") (pintype "passive"))
      (node (ref "C52") (pin "2") (pinfunction "2_2") (pintype "passive"))
      (node (ref "J7") (pin "2") (pintype "passive"))
      (node (ref "R22") (pin "2") (pinfunction "2_2") (pintype "passive"))
      (node (ref "R25") (pin "2") (pinfunction "2_2") (pintype "passive"))
      (node (ref "U8") (pin "8") (pinfunction "OUT_8") (pintype "passive"))
      (node (ref "U8") (pin "9") (pinfunction "OUT_9") (pintype "passive"))
    )
    (net (code "19") (name "Net-(C53-Pad2)") (class "Default")
      (node (ref "C53") (pin "2") (pinfunction "2_2") (pintype "passive"))
      (node (ref "C54") (pin "2") (pinfunction "2_2") (pintype "passive"))
      (node (ref "J8") (pin "2") (pintype "passive"))
      (node (ref "R23") (pin "2") (pinfunction "2_2") (pintype "passive"))
      (node (ref "R26") (pin "2") (pinfunction "2_2") (pintype "passive"))
      (node (ref "U9") (pin "8") (pinfunction "OUT_8") (pintype "passive"))
      (node (ref "U9") (pin "9") (pinfunction "OUT_9") (pintype "passive"))
    )
    (net (code "20") (name "Net-(C55-Pad2)") (class "Default")
      (node (ref "C55") (pin "2") (pinfunction "2_2") (pintype "passive"))
      (node (ref "C56") (pin "2") (pinfunction "2_2") (pintype "passive"))
      (node (ref "J9") (pin "2") (pintype "passive"))
      (node (ref "R24") (pin "2") (pinfunction "2_2") (pintype "passive"))
      (node (ref "R27") (pin "2") (pinfunction "2_2") (pintype "passive"))
      (node (ref "U10") (pin "8") (pinfunction "OUT_8") (pintype "passive"))
      (node (ref "U10") (pin "9") (pinfunction "OUT_9") (pintype "passive"))
    )
    (net (code "21") (name "Net-(R1-Pad2)") (class "Default")
      (node (ref "R1") (pin "2") (pinfunction "2_2") (pintype "passive"))
      (node (ref "R97") (pin "2") (pinfunction "2_2") (pintype "passive"))
    )
    (net (code "22") (name "Net-(R1-Pad3)") (class "Default")
      (node (ref "R1") (pin "3") (pinfunction "3_3") (pintype "passive"))
      (node (ref "R98") (pin "2") (pinfunction "2_2") (pintype "passive"))
    )
    (net (code "23") (name "Net-(R15-Pad2)") (class "Default")
      (node (ref "R15") (pin "2") (pinfunction "2_2") (pintype "passive"))
      (node (ref "R99") (pin "2") (pinfunction "2_2") (pintype "passive"))
    )
    (net (code "24") (name "Net-(R100-Pad2)") (class "Default")
      (node (ref "R100") (pin "2") (pinfunction "2_2") (pintype "passive"))
      (node (ref "R15") (pin "3") (pinfunction "3_3") (pintype "passive"))
    )
    (net (code "25") (name "Net-(R101-Pad2)") (class "Default")
      (node (ref "R101") (pin "2") (pinfunction "2_2") (pintype "passive"))
      (node (ref "R18") (pin "2") (pinfunction "2_2") (pintype "passive"))
    )
    (net (code "26") (name "Net-(R102-Pad2)") (class "Default")
      (node (ref "R102") (pin "2") (pinfunction "2_2") (pintype "passive"))
      (node (ref "R18") (pin "3") (pinfunction "3_3") (pintype "passive"))
    )
    (net (code "27") (name "Net-(U1-SCLB)") (class "Default")
      (node (ref "R2") (pin "1") (pinfunction "1_1") (pintype "passive"))
      (node (ref "U1") (pin "5") (pinfunction "SCLB_5") (pintype "input"))
      (node (ref "U4") (pin "6") (pinfunction "SCL_6") (pintype "input"))
    )
    (net (code "28") (name "Net-(U1-SDAB)") (class "Default")
      (node (ref "R3") (pin "1") (pinfunction "1_1") (pintype "passive"))
      (node (ref "U1") (pin "4") (pinfunction "SDAB_4") (pintype "bidirectional"))
      (node (ref "U4") (pin "7") (pinfunction "SDA_7") (pintype "bidirectional"))
    )
    (net (code "29") (name "Net-(U3-BIAS)") (class "Default")
      (node (ref "C29") (pin "2") (pinfunction "2_2") (pintype "passive"))
      (node (ref "U3") (pin "13") (pinfunction "BIAS_13") (pintype "output"))
      (node (ref "U3") (pin "16") (pinfunction "FB_16") (pintype "input"))
    )
    (net (code "30") (name "Net-(U3-BST)") (class "Default")
      (node (ref "C22") (pin "2") (pinfunction "2_2") (pintype "passive"))
      (node (ref "U3") (pin "3") (pinfunction "BST_3") (pintype "passive"))
    )
    (net (code "31") (name "Net-(U3-COMP)") (class "Default")
      (node (ref "C31") (pin "2") (pinfunction "2_2") (pintype "passive"))
      (node (ref "R12") (pin "2") (pinfunction "2_2") (pintype "passive"))
      (node (ref "U3") (pin "15") (pinfunction "COMP_15") (pintype "output"))
    )
    (net (code "32") (name "Net-(U3-EN)") (class "Default")
      (node (ref "C12") (pin "2") (pinfunction "2_2") (pintype "passive"))
      (node (ref "C13") (pin "2") (pinfunction "2_2") (pintype "passive"))
      (node (ref "C14") (pin "2") (pinfunction "2_2") (pintype "passive"))
      (node (ref "C15") (pin "2") (pinfunction "2_2") (pintype "passive"))
      (node (ref "C16") (pin "2") (pinfunction "2_2") (pintype "passive"))
      (node (ref "C17") (pin "2") (pinfunction "2_2") (pintype "passive"))
      (node (ref "C18") (pin "2") (pinfunction "2_2") (pintype "passive"))
      (node (ref "C19") (pin "2") (pinfunction "2_2") (pintype "passive"))
      (node (ref "J2") (pin "1") (pinfunction "1_1") (pintype "passive"))
      (node (ref "U3") (pin "10") (pinfunction "SUP_10") (pintype "input"))
      (node (ref "U3") (pin "11") (pinfunction "EN_11") (pintype "input"))
      (node (ref "U3") (pin "9") (pinfunction "SUPSW_9") (pintype "input"))
    )
    (net (code "33") (name "Net-(U3-FOSC)") (class "Default")
      (node (ref "R10") (pin "2") (pinfunction "2_2") (pintype "passive"))
      (node (ref "U3") (pin "17") (pinfunction "FOSC_17") (pintype "input"))
    )
    (net (code "34") (name "Net-(U3-LX)") (class "Default")
      (node (ref "C22") (pin "1") (pinfunction "1_1") (pintype "passive"))
      (node (ref "L1") (pin "2") (pinfunction "2_2") (pintype "passive"))
      (node (ref "U3") (pin "6") (pinfunction "LX_6") (pintype "passive"))
    )
    (net (code "35") (name "Net-(U6-FB)") (class "Default")
      (node (ref "R14") (pin "1") (pinfunction "1_1") (pintype "passive"))
      (node (ref "R20") (pin "2") (pinfunction "2_2") (pintype "passive"))
      (node (ref "U6") (pin "13") (pinfunction "FB_13") (pintype "passive"))
    )
    (net (code "36") (name "Net-(U6-OUT_SENSE)") (class "Default")
      (node (ref "R17") (pin "1") (pinfunction "1_1") (pintype "passive"))
      (node (ref "U6") (pin "10") (pinfunction "OUT_SENSE_10") (pintype "passive"))
    )
    (net (code "37") (name "Net-(U6-SW-Pad4)") (class "Default")
      (node (ref "U6") (pin "4") (pinfunction "SW_4") (pintype "passive"))
      (node (ref "U6") (pin "5") (pinfunction "SW_5") (pintype "passive"))
      (node (ref "U6") (pin "6") (pinfunction "SW_6") (pintype "passive"))
      (node (ref "U6") (pin "7") (pinfunction "SW_7") (pintype "passive"))
    )
    (net (code "38") (name "Net-(U8-FB)") (class "Default")
      (node (ref "R22") (pin "1") (pinfunction "1_1") (pintype "passive"))
      (node (ref "R28") (pin "2") (pinfunction "2_2") (pintype "passive"))
      (node (ref "U8") (pin "13") (pinfunction "FB_13") (pintype "passive"))
    )
    (net (code "39") (name "Net-(U8-OUT_SENSE)") (class "Default")
      (node (ref "R25") (pin "1") (pinfunction "1_1") (pintype "passive"))
      (node (ref "U8") (pin "10") (pinfunction "OUT_SENSE_10") (pintype "passive"))
    )
    (net (code "40") (name "Net-(U8-SW-Pad4)") (class "Default")
      (node (ref "U8") (pin "4") (pinfunction "SW_4") (pintype "passive"))
      (node (ref "U8") (pin "5") (pinfunction "SW_5") (pintype "passive"))
      (node (ref "U8") (pin "6") (pinfunction "SW_6") (pintype "passive"))
      (node (ref "U8") (pin "7") (pinfunction "SW_7") (pintype "passive"))
    )
    (net (code "41") (name "Net-(U9-FB)") (class "Default")
      (node (ref "R23") (pin "1") (pinfunction "1_1") (pintype "passive"))
      (node (ref "R29") (pin "2") (pinfunction "2_2") (pintype "passive"))
      (node (ref "U9") (pin "13") (pinfunction "FB_13") (pintype "passive"))
    )
    (net (code "42") (name "Net-(U9-OUT_SENSE)") (class "Default")
      (node (ref "R26") (pin "1") (pinfunction "1_1") (pintype "passive"))
      (node (ref "U9") (pin "10") (pinfunction "OUT_SENSE_10") (pintype "passive"))
    )
    (net (code "43") (name "Net-(U9-SW-Pad4)") (class "Default")
      (node (ref "U9") (pin "4") (pinfunction "SW_4") (pintype "passive"))
      (node (ref "U9") (pin "5") (pinfunction "SW_5") (pintype "passive"))
      (node (ref "U9") (pin "6") (pinfunction "SW_6") (pintype "passive"))
      (node (ref "U9") (pin "7") (pinfunction "SW_7") (pintype "passive"))
    )
    (net (code "44") (name "Net-(U10-FB)") (class "Default")
      (node (ref "R24") (pin "1") (pinfunction "1_1") (pintype "passive"))
      (node (ref "R30") (pin "2") (pinfunction "2_2") (pintype "passive"))
      (node (ref "U10") (pin "13") (pinfunction "FB_13") (pintype "passive"))
    )
    (net (code "45") (name "Net-(U10-OUT_SENSE)") (class "Default")
      (node (ref "R27") (pin "1") (pinfunction "1_1") (pintype "passive"))
      (node (ref "U10") (pin "10") (pinfunction "OUT_SENSE_10") (pintype "passive"))
    )
    (net (code "46") (name "Net-(U10-SW-Pad4)") (class "Default")
      (node (ref "U10") (pin "4") (pinfunction "SW_4") (pintype "passive"))
      (node (ref "U10") (pin "5") (pinfunction "SW_5") (pintype "passive"))
      (node (ref "U10") (pin "6") (pinfunction "SW_6") (pintype "passive"))
      (node (ref "U10") (pin "7") (pinfunction "SW_7") (pintype "passive"))
    )
    (net (code "47") (name "PL_1V8") (class "Default") (node (ref "J7") (pin "1") (pintype "passive")))
    (net (code "48") (name "PL_3V3") (class "Default") (node (ref "J8") (pin "1") (pintype "passive")))
    (net (code "49") (name "PL_5V0") (class "Default")
      (node (ref "C45") (pin "2") (pinfunction "2_2") (pintype "passive"))
      (node (ref "C46") (pin "2") (pinfunction "2_2") (pintype "passive"))
      (node (ref "C47") (pin "2") (pinfunction "2_2") (pintype "passive"))
      (node (ref "C48") (pin "2") (pinfunction "2_2") (pintype "passive"))
      (node (ref "R18") (pin "4") (pinfunction "4_4") (pintype "passive"))
      (node (ref "U8") (pin "17") (pinfunction "VIN_17") (pintype "passive"))
      (node (ref "U8") (pin "18") (pinfunction "VIN_18") (pintype "passive"))
      (node (ref "U9") (pin "17") (pinfunction "VIN_17") (pintype "passive"))
      (node (ref "U9") (pin "18") (pinfunction "VIN_18") (pintype "passive"))
    )
    (net (code "50") (name "PS_1V8") (class "Default")
      (node (ref "C2") (pin "2") (pinfunction "2_2") (pintype "passive"))
      (node (ref "J9") (pin "1") (pintype "passive"))
      (node (ref "U1") (pin "7") (pinfunction "VCC(A)_7") (pintype "power_in"))
    )
    (net (code "51") (name "PS_3V3") (class "Default") (node (ref "J5") (pin "1") (pintype "passive")))
    (net (code "52") (name "PS_5V0") (class "Default")
      (node (ref "C35") (pin "2") (pinfunction "2_2") (pintype "passive"))
      (node (ref "C36") (pin "2") (pinfunction "2_2") (pintype "passive"))
      (node (ref "C49") (pin "2") (pinfunction "2_2") (pintype "passive"))
      (node (ref "C50") (pin "2") (pinfunction "2_2") (pintype "passive"))
      (node (ref "R15") (pin "4") (pinfunction "4_4") (pintype "passive"))
      (node (ref "U10") (pin "17") (pinfunction "VIN_17") (pintype "passive"))
      (node (ref "U10") (pin "18") (pinfunction "VIN_18") (pintype "passive"))
      (node (ref "U6") (pin "17") (pinfunction "VIN_17") (pintype "passive"))
      (node (ref "U6") (pin "18") (pinfunction "VIN_18") (pintype "passive"))
    )
    (net (code "53") (name "SOM_5V0") (class "Default")
      (node (ref "R1") (pin "4") (pinfunction "4_4") (pintype "passive"))
    )
    (net (code "54") (name "unconnected-(U1-EN-Pad3)") (class "Default")
      (node (ref "U1") (pin "3") (pinfunction "EN_3") (pintype "input+no_connect"))
    )
    (net (code "55") (name "unconnected-(U4-CRITICAL-Pad9)") (class "Default")
      (node (ref "U4") (pin "9") (pinfunction "CRITICAL_9") (pintype "open_collector"))
    )
    (net (code "56") (name "unconnected-(U4-PV-Pad10)") (class "Default")
      (node (ref "U4") (pin "10") (pinfunction "PV_10") (pintype "open_collector"))
    )
    (net (code "57") (name "unconnected-(U4-TC-Pad13)") (class "Default")
      (node (ref "U4") (pin "13") (pinfunction "TC_13") (pintype "open_collector"))
    )
    (net (code "58") (name "unconnected-(U4-WARNING-Pad8)") (class "Default")
      (node (ref "U4") (pin "8") (pinfunction "WARNING_8") (pintype "open_collector"))
    )
    (net (code "59") (name "unconnected-(U6-BST-Pad3)") (class "Default")
      (node (ref "U6") (pin "3") (pinfunction "BST_3") (pintype "passive"))
    )
    (net (code "60") (name "unconnected-(U6-VCC-Pad16)") (class "Default")
      (node (ref "U6") (pin "16") (pinfunction "VCC_16") (pintype "passive"))
    )
    (net (code "61") (name "unconnected-(U8-BST-Pad3)") (class "Default")
      (node (ref "U8") (pin "3") (pinfunction "BST_3") (pintype "passive"))
    )
    (net (code "62") (name "unconnected-(U8-VCC-Pad16)") (class "Default")
      (node (ref "U8") (pin "16") (pinfunction "VCC_16") (pintype "passive"))
    )
    (net (code "63") (name "unconnected-(U9-BST-Pad3)") (class "Default")
      (node (ref "U9") (pin "3") (pinfunction "BST_3") (pintype "passive"))
    )
    (net (code "64") (name "unconnected-(U9-VCC-Pad16)") (class "Default")
      (node (ref "U9") (pin "16") (pinfunction "VCC_16") (pintype "passive"))
    )
    (net (code "65") (name "unconnected-(U10-BST-Pad3)") (class "Default")
      (node (ref "U10") (pin "3") (pinfunction "BST_3") (pintype "passive"))
    )
    (net (code "66") (name "unconnected-(U10-VCC-Pad16)") (class "Default")
      (node (ref "U10") (pin "16") (pinfunction "VCC_16") (pintype "passive"))
    )
  )
)
